# TOF.net
KiCad netlist of a schematic drawn in Altium Designer
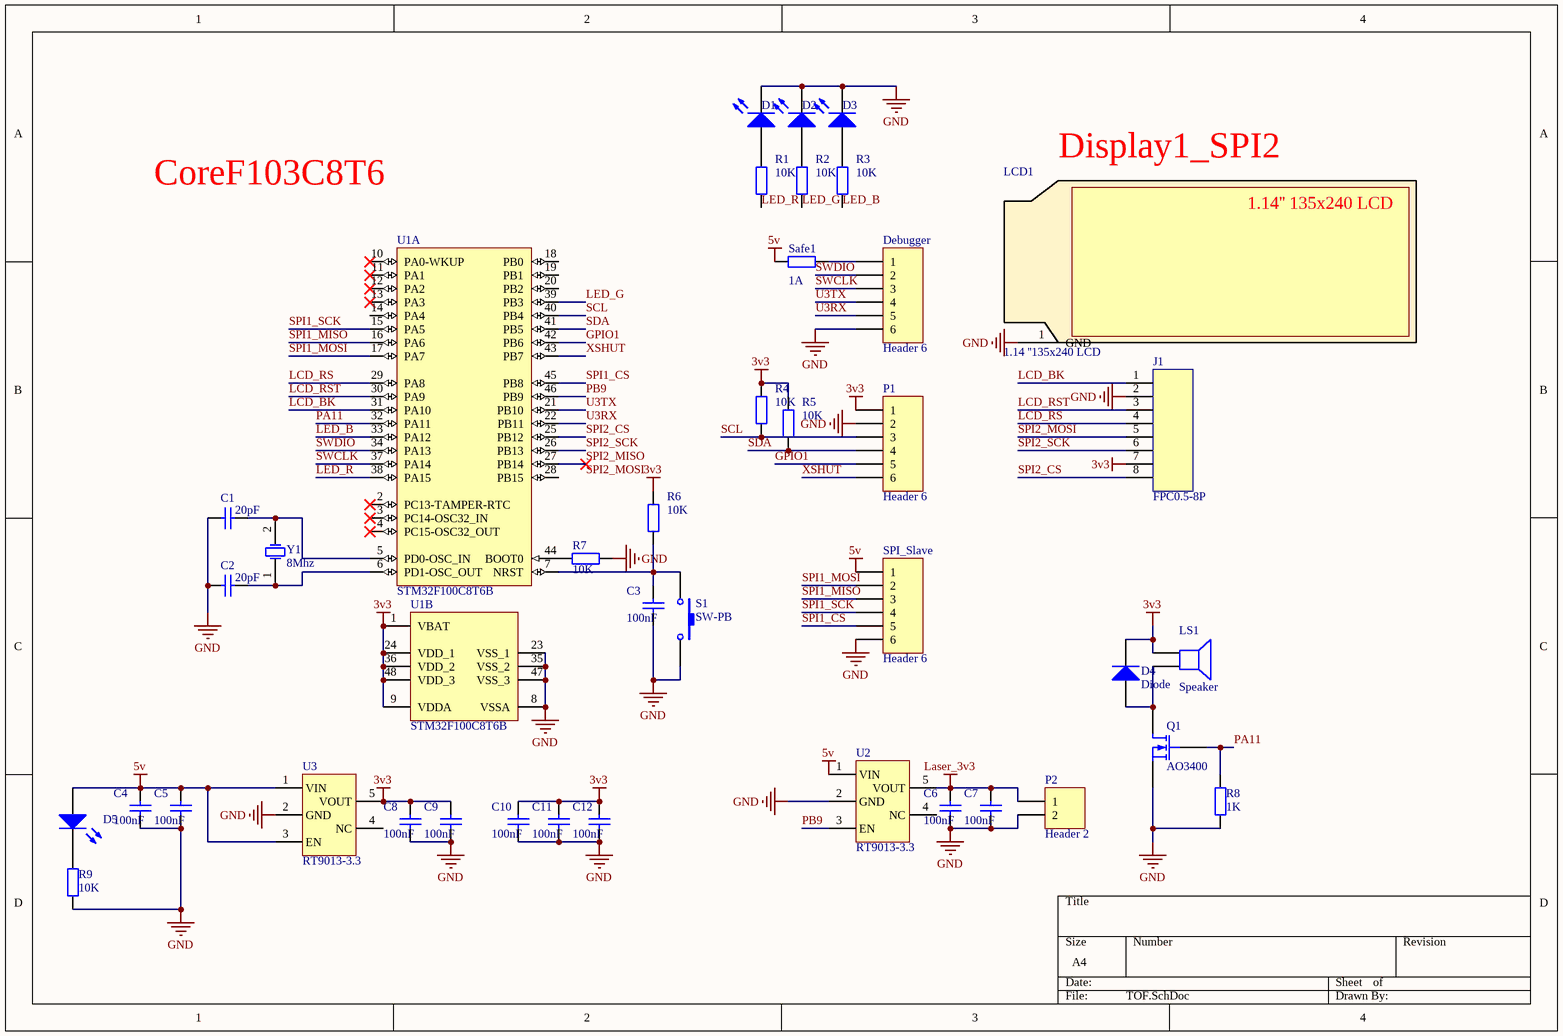
[diagram p0: TOF.SchDoc]

(export (version "E")
  (design (tool "Eeschema 10.0.6"))
  (components
    (comp (ref "C1")
      (value "20pF")
      (footprint "0603C")
      (description "Capacitor")
      (fields (field (name "Comment") "Cap") (field (name "PUBLISHER") "Altium Limited"))
      (libsource (lib "Miscellaneous Devices") (part "Cap"))
    )
    (comp (ref "C2")
      (value "20pF")
      (footprint "0603C")
      (description "Capacitor")
      (fields (field (name "Comment") "Cap") (field (name "PUBLISHER") "Altium Limited"))
      (libsource (lib "Miscellaneous Devices") (part "Cap"))
    )
    (comp (ref "C3")
      (value "100nF")
      (footprint "0603C")
      (description "Capacitor")
      (fields (field (name "Comment") "Cap") (field (name "PUBLISHER") "Altium Limited"))
      (libsource (lib "Miscellaneous Devices") (part "Cap"))
    )
    (comp (ref "C4")
      (value "100nF")
      (footprint "0603C")
      (description "Capacitor")
      (fields (field (name "Comment") "Cap") (field (name "PUBLISHER") "Altium Limited"))
      (libsource (lib "Miscellaneous Devices") (part "Cap"))
    )
    (comp (ref "C5")
      (value "100nF")
      (footprint "0603C")
      (description "Capacitor")
      (fields (field (name "Comment") "Cap") (field (name "PUBLISHER") "Altium Limited"))
      (libsource (lib "Miscellaneous Devices") (part "Cap"))
    )
    (comp (ref "C6")
      (value "100nF")
      (footprint "0603C")
      (description "Capacitor")
      (fields (field (name "Comment") "Cap") (field (name "PUBLISHER") "Altium Limited"))
      (libsource (lib "Miscellaneous Devices") (part "Cap"))
    )
    (comp (ref "C7")
      (value "100nF")
      (footprint "0603C")
      (description "Capacitor")
      (fields (field (name "Comment") "Cap") (field (name "PUBLISHER") "Altium Limited"))
      (libsource (lib "Miscellaneous Devices") (part "Cap"))
    )
    (comp (ref "C8")
      (value "100nF")
      (footprint "0603C")
      (description "Capacitor")
      (fields (field (name "Comment") "Cap") (field (name "PUBLISHER") "Altium Limited"))
      (libsource (lib "Miscellaneous Devices") (part "Cap"))
    )
    (comp (ref "C9")
      (value "100nF")
      (footprint "0603C")
      (description "Capacitor")
      (fields (field (name "Comment") "Cap") (field (name "PUBLISHER") "Altium Limited"))
      (libsource (lib "Miscellaneous Devices") (part "Cap"))
    )
    (comp (ref "C10")
      (value "100nF")
      (footprint "0603C")
      (description "Capacitor")
      (fields (field (name "Comment") "Cap") (field (name "PUBLISHER") "Altium Limited"))
      (libsource (lib "Miscellaneous Devices") (part "Cap"))
    )
    (comp (ref "C11")
      (value "100nF")
      (footprint "0603C")
      (description "Capacitor")
      (fields (field (name "Comment") "Cap") (field (name "PUBLISHER") "Altium Limited"))
      (libsource (lib "Miscellaneous Devices") (part "Cap"))
    )
    (comp (ref "C12")
      (value "100nF")
      (footprint "0603C")
      (description "Capacitor")
      (fields (field (name "Comment") "Cap") (field (name "PUBLISHER") "Altium Limited"))
      (libsource (lib "Miscellaneous Devices") (part "Cap"))
    )
    (comp (ref "D1")
      (value "LED0")
      (footprint "LED-0805-Red")
      (description "Typical INFRARED GaAs LED")
      (fields (field (name "PUBLISHER") "Altium Limited"))
      (libsource (lib "Miscellaneous Devices") (part "LED0"))
    )
    (comp (ref "D2")
      (value "LED0")
      (footprint "0805LED")
      (description "Typical INFRARED GaAs LED")
      (fields (field (name "PUBLISHER") "Altium Limited"))
      (libsource (lib "Miscellaneous Devices") (part "LED0"))
    )
    (comp (ref "D3")
      (value "LED0")
      (footprint "LED-0805-Blue")
      (description "Typical INFRARED GaAs LED")
      (fields (field (name "PUBLISHER") "Altium Limited"))
      (libsource (lib "Miscellaneous Devices") (part "LED0"))
    )
    (comp (ref "D4")
      (value "Diode")
      (footprint "SOD-323-")
      (description "Default Diode")
      (fields (field (name "PUBLISHER") "Altium Limited"))
      (libsource (lib "Miscellaneous Devices") (part "Diode"))
    )
    (comp (ref "D5")
      (value "LED0")
      (footprint "0805LED")
      (description "Typical INFRARED GaAs LED")
      (fields (field (name "PUBLISHER") "Altium Limited"))
      (libsource (lib "Miscellaneous Devices") (part "LED0"))
    )
    (comp (ref "Debugger")
      (value "Header 6")
      (footprint "GX1.25_T_6P")
      (description "Header, 6-Pin")
      (fields (field (name "PUBLISHER") "Altium Limited"))
      (libsource (lib "Miscellaneous Connectors") (part "Header 6"))
    )
    (comp (ref "J1")
      (value "FPC0.5-8P")
      (footprint "FPC0.5-8P")
      (description "贴片")
      (libsource (lib "TOF") (part "FPC0.5-8P"))
    )
    (comp (ref "LCD1")
      (value "1.14 ''135x240 LCD")
      (footprint "1.14'' LCD")
      (libsource (lib "TOF") (part "1.14 ''135x240 LCD"))
    )
    (comp (ref "LS1")
      (value "Speaker")
      (footprint "MLT-8530")
      (description "Loudspeaker")
      (fields (field (name "PUBLISHER") "Altium Limited"))
      (libsource (lib "Miscellaneous Devices") (part "Speaker"))
    )
    (comp (ref "P1")
      (value "Header 6")
      (footprint "HDR1X6")
      (description "Header, 6-Pin")
      (fields (field (name "PUBLISHER") "Altium Limited"))
      (libsource (lib "Miscellaneous Connectors") (part "Header 6"))
    )
    (comp (ref "P2")
      (value "Header 2")
      (footprint "HDR1X2")
      (description "Header, 2-Pin")
      (fields (field (name "PUBLISHER") "Altium Limited"))
      (libsource (lib "Miscellaneous Connectors") (part "Header 2"))
    )
    (comp (ref "Q1")
      (value "AO3400")
      (footprint "SOT-23")
      (description "N-Channel MOSFET")
      (fields (field (name "PUBLISHER") "Altium Limited"))
      (libsource (lib "Miscellaneous Devices") (part "MOSFET-N"))
    )
    (comp (ref "R1")
      (value "10K")
      (footprint "0603R")
      (description "Resistor")
      (fields (field (name "PUBLISHER") "Altium Limited"))
      (libsource (lib "") (part "Res2_1"))
    )
    (comp (ref "R2")
      (value "10K")
      (footprint "0603R")
      (description "Resistor")
      (fields (field (name "PUBLISHER") "Altium Limited"))
      (libsource (lib "") (part "Res2_1"))
    )
    (comp (ref "R3")
      (value "10K")
      (footprint "0603R")
      (description "Resistor")
      (fields (field (name "PUBLISHER") "Altium Limited"))
      (libsource (lib "") (part "Res2_1"))
    )
    (comp (ref "R4")
      (value "10K")
      (footprint "0603R")
      (description "Resistor")
      (fields (field (name "PUBLISHER") "Altium Limited"))
      (libsource (lib "") (part "Res2_1"))
    )
    (comp (ref "R5")
      (value "10K")
      (footprint "0603R")
      (description "Resistor")
      (fields (field (name "PUBLISHER") "Altium Limited"))
      (libsource (lib "") (part "Res2_1"))
    )
    (comp (ref "R6")
      (value "10K")
      (footprint "0603R")
      (description "Resistor")
      (fields (field (name "PUBLISHER") "Altium Limited"))
      (libsource (lib "") (part "Res2_1"))
    )
    (comp (ref "R7")
      (value "10K")
      (footprint "0603R")
      (description "Resistor")
      (fields (field (name "Comment") "Res2") (field (name "PUBLISHER") "Altium Limited"))
      (libsource (lib "") (part "Res2_3"))
    )
    (comp (ref "R8")
      (value "1K")
      (footprint "0603R")
      (description "Resistor")
      (fields (field (name "Comment") "Res2") (field (name "PUBLISHER") "Altium Limited"))
      (libsource (lib "") (part "Res2_1"))
    )
    (comp (ref "R9")
      (value "10K")
      (footprint "0603R")
      (description "Resistor")
      (fields (field (name "PUBLISHER") "Altium Limited"))
      (libsource (lib "") (part "Res2_2"))
    )
    (comp (ref "S1")
      (value "SW-PB")
      (footprint "Key-2*4*3.5-S")
      (description "Switch")
      (fields (field (name "PUBLISHER") "Altium Limited"))
      (libsource (lib "Miscellaneous Devices") (part "SW-PB"))
    )
    (comp (ref "Safe1")
      (value "1A")
      (footprint "Maxwell_LIB:0805R")
      (description "Resistor")
      (fields (field (name "Comment") "Res2") (field (name "PUBLISHER") "Altium Limited"))
      (libsource (lib "Miscellaneous Devices") (part "Res2"))
    )
    (comp (ref "SPI_Slave")
      (value "Header 6")
      (footprint "GX1.25_T_6P")
      (description "Header, 6-Pin")
      (fields (field (name "PUBLISHER") "Altium Limited"))
      (libsource (lib "Miscellaneous Connectors") (part "Header 6"))
    )
    (comp (ref "U1")
      (value "STM32F100C8T6B")
      (footprint "STM-LQFP48_N")
      (libsource (lib "STM32F1") (part "STM32F100C8T6B"))
    )
    (comp (ref "U2")
      (value "RT9013-3.3")
      (footprint "SOT-23-5")
      (description "3.3V 500mA")
      (libsource (lib "My_Library") (part "RT9013"))
    )
    (comp (ref "U3")
      (value "RT9013-3.3")
      (footprint "SOT-23-5")
      (description "3.3V 500mA")
      (libsource (lib "My_Library") (part "RT9013"))
    )
    (comp (ref "Y1")
      (value "8Mhz")
      (footprint "Cry-3215")
      (fields (field (name "PUBLISHER") "Altium Limited"))
      (libsource (lib "Miscellaneous Devices") (part "XTAL"))
    )
  )
  (nets
    (net (code "1") (name "/GPIO1") (class "Default")
      (node (ref "P1") (pin "5") (pinfunction "5_5") (pintype "passive"))
      (node (ref "U1") (pin "42") (pinfunction "PB6_42") (pintype "bidirectional"))
    )
    (net (code "2") (name "/LCD_BK") (class "Default")
      (node (ref "J1") (pin "1") (pinfunction "1_1") (pintype "passive"))
      (node (ref "U1") (pin "31") (pinfunction "PA10_31") (pintype "bidirectional"))
    )
    (net (code "3") (name "/LCD_RS") (class "Default")
      (node (ref "J1") (pin "4") (pinfunction "4_4") (pintype "passive"))
      (node (ref "U1") (pin "29") (pinfunction "PA8_29") (pintype "bidirectional"))
    )
    (net (code "4") (name "/LCD_RST") (class "Default")
      (node (ref "J1") (pin "3") (pinfunction "3_3") (pintype "passive"))
      (node (ref "U1") (pin "30") (pinfunction "PA9_30") (pintype "bidirectional"))
    )
    (net (code "5") (name "/LED_B") (class "Default")
      (node (ref "R3") (pin "1") (pinfunction "1_1") (pintype "passive"))
      (node (ref "U1") (pin "33") (pinfunction "PA12_33") (pintype "bidirectional"))
    )
    (net (code "6") (name "/LED_G") (class "Default")
      (node (ref "R2") (pin "1") (pinfunction "1_1") (pintype "passive"))
      (node (ref "U1") (pin "39") (pinfunction "PB3_39") (pintype "bidirectional"))
    )
    (net (code "7") (name "/LED_R") (class "Default")
      (node (ref "R1") (pin "1") (pinfunction "1_1") (pintype "passive"))
      (node (ref "U1") (pin "38") (pinfunction "PA15_38") (pintype "bidirectional"))
    )
    (net (code "8") (name "/PA11") (class "Default")
      (node (ref "Q1") (pin "2") (pinfunction "G_2") (pintype "passive"))
      (node (ref "R8") (pin "2") (pinfunction "2_2") (pintype "passive"))
      (node (ref "U1") (pin "32") (pinfunction "PA11_32") (pintype "bidirectional"))
    )
    (net (code "9") (name "/PB9") (class "Default")
      (node (ref "U1") (pin "46") (pinfunction "PB9_46") (pintype "bidirectional"))
      (node (ref "U2") (pin "3") (pinfunction "EN_3") (pintype "passive"))
    )
    (net (code "10") (name "/SCL") (class "Default")
      (node (ref "P1") (pin "3") (pinfunction "3_3") (pintype "passive"))
      (node (ref "R4") (pin "1") (pinfunction "1_1") (pintype "passive"))
      (node (ref "U1") (pin "40") (pinfunction "PB4_40") (pintype "bidirectional"))
    )
    (net (code "11") (name "/SDA") (class "Default")
      (node (ref "P1") (pin "4") (pinfunction "4_4") (pintype "passive"))
      (node (ref "R5") (pin "1") (pinfunction "1_1") (pintype "passive"))
      (node (ref "U1") (pin "41") (pinfunction "PB5_41") (pintype "bidirectional"))
    )
    (net (code "12") (name "/SPI1_CS") (class "Default")
      (node (ref "SPI_Slave") (pin "5") (pinfunction "5_5") (pintype "passive"))
      (node (ref "U1") (pin "45") (pinfunction "PB8_45") (pintype "bidirectional"))
    )
    (net (code "13") (name "/SPI1_MISO") (class "Default")
      (node (ref "SPI_Slave") (pin "3") (pinfunction "3_3") (pintype "passive"))
      (node (ref "U1") (pin "16") (pinfunction "PA6_16") (pintype "bidirectional"))
    )
    (net (code "14") (name "/SPI1_MOSI") (class "Default")
      (node (ref "SPI_Slave") (pin "2") (pinfunction "2_2") (pintype "passive"))
      (node (ref "U1") (pin "17") (pinfunction "PA7_17") (pintype "bidirectional"))
    )
    (net (code "15") (name "/SPI1_SCK") (class "Default")
      (node (ref "SPI_Slave") (pin "4") (pinfunction "4_4") (pintype "passive"))
      (node (ref "U1") (pin "15") (pinfunction "PA5_15") (pintype "bidirectional"))
    )
    (net (code "16") (name "/SPI2_CS") (class "Default")
      (node (ref "J1") (pin "8") (pinfunction "8_8") (pintype "passive"))
      (node (ref "U1") (pin "25") (pinfunction "PB12_25") (pintype "bidirectional"))
    )
    (net (code "17") (name "/SPI2_MISO") (class "Default")
      (node (ref "U1") (pin "27") (pinfunction "PB14_27") (pintype "bidirectional+no_connect"))
    )
    (net (code "18") (name "/SPI2_MOSI") (class "Default")
      (node (ref "J1") (pin "5") (pinfunction "5_5") (pintype "passive"))
    )
    (net (code "19") (name "/SPI2_SCK") (class "Default")
      (node (ref "J1") (pin "6") (pinfunction "6_6") (pintype "passive"))
      (node (ref "U1") (pin "26") (pinfunction "PB13_26") (pintype "bidirectional"))
    )
    (net (code "20") (name "/SWCLK") (class "Default")
      (node (ref "Debugger") (pin "3") (pinfunction "3_3") (pintype "passive"))
      (node (ref "U1") (pin "37") (pinfunction "PA14_37") (pintype "bidirectional"))
    )
    (net (code "21") (name "/SWDIO") (class "Default")
      (node (ref "Debugger") (pin "2") (pinfunction "2_2") (pintype "passive"))
      (node (ref "U1") (pin "34") (pinfunction "PA13_34") (pintype "bidirectional"))
    )
    (net (code "22") (name "/U3RX") (class "Default")
      (node (ref "Debugger") (pin "5") (pinfunction "5_5") (pintype "passive"))
      (node (ref "U1") (pin "22") (pinfunction "PB11_22") (pintype "bidirectional"))
    )
    (net (code "23") (name "/U3TX") (class "Default")
      (node (ref "Debugger") (pin "4") (pinfunction "4_4") (pintype "passive"))
      (node (ref "U1") (pin "21") (pinfunction "PB10_21") (pintype "bidirectional"))
    )
    (net (code "24") (name "/XSHUT") (class "Default")
      (node (ref "P1") (pin "6") (pinfunction "6_6") (pintype "passive"))
      (node (ref "U1") (pin "43") (pinfunction "PB7_43") (pintype "bidirectional"))
    )
    (net (code "25") (name "3v3") (class "Default")
      (node (ref "C10") (pin "2") (pinfunction "2_2") (pintype "passive"))
      (node (ref "C11") (pin "2") (pinfunction "2_2") (pintype "passive"))
      (node (ref "C12") (pin "2") (pinfunction "2_2") (pintype "passive"))
      (node (ref "C8") (pin "2") (pinfunction "2_2") (pintype "passive"))
      (node (ref "C9") (pin "2") (pinfunction "2_2") (pintype "passive"))
      (node (ref "D4") (pin "2") (pinfunction "K_2") (pintype "passive"))
      (node (ref "J1") (pin "7") (pinfunction "7_7") (pintype "passive"))
      (node (ref "LS1") (pin "1") (pinfunction "1_1") (pintype "passive"))
      (node (ref "P1") (pin "1") (pinfunction "1_1") (pintype "passive"))
      (node (ref "R4") (pin "2") (pinfunction "2_2") (pintype "passive"))
      (node (ref "R5") (pin "2") (pinfunction "2_2") (pintype "passive"))
      (node (ref "R6") (pin "2") (pinfunction "2_2") (pintype "passive"))
      (node (ref "U1") (pin "1") (pinfunction "VBAT_1") (pintype "power_in"))
      (node (ref "U1") (pin "24") (pinfunction "VDD_1_24") (pintype "power_in"))
      (node (ref "U1") (pin "36") (pinfunction "VDD_2_36") (pintype "power_in"))
      (node (ref "U1") (pin "48") (pinfunction "VDD_3_48") (pintype "power_in"))
      (node (ref "U1") (pin "9") (pinfunction "VDDA_9") (pintype "power_in"))
      (node (ref "U3") (pin "5") (pinfunction "VOUT_5") (pintype "passive"))
    )
    (net (code "26") (name "5v") (class "Default")
      (node (ref "C4") (pin "2") (pinfunction "2_2") (pintype "passive"))
      (node (ref "C5") (pin "2") (pinfunction "2_2") (pintype "passive"))
      (node (ref "D5") (pin "1") (pinfunction "A_1") (pintype "passive"))
      (node (ref "SPI_Slave") (pin "1") (pinfunction "1_1") (pintype "passive"))
      (node (ref "Safe1") (pin "1") (pinfunction "1_1") (pintype "passive"))
      (node (ref "U2") (pin "1") (pinfunction "VIN_1") (pintype "passive"))
      (node (ref "U3") (pin "1") (pinfunction "VIN_1") (pintype "passive"))
      (node (ref "U3") (pin "3") (pinfunction "EN_3") (pintype "passive"))
    )
    (net (code "27") (name "GND") (class "Default")
      (node (ref "C1") (pin "1") (pinfunction "1_1") (pintype "passive"))
      (node (ref "C10") (pin "1") (pinfunction "1_1") (pintype "passive"))
      (node (ref "C11") (pin "1") (pinfunction "1_1") (pintype "passive"))
      (node (ref "C12") (pin "1") (pinfunction "1_1") (pintype "passive"))
      (node (ref "C2") (pin "1") (pinfunction "1_1") (pintype "passive"))
      (node (ref "C3") (pin "1") (pinfunction "1_1") (pintype "passive"))
      (node (ref "C4") (pin "1") (pinfunction "1_1") (pintype "passive"))
      (node (ref "C5") (pin "1") (pinfunction "1_1") (pintype "passive"))
      (node (ref "C6") (pin "1") (pinfunction "1_1") (pintype "passive"))
      (node (ref "C7") (pin "1") (pinfunction "1_1") (pintype "passive"))
      (node (ref "C8") (pin "1") (pinfunction "1_1") (pintype "passive"))
      (node (ref "C9") (pin "1") (pinfunction "1_1") (pintype "passive"))
      (node (ref "D1") (pin "2") (pinfunction "K_2") (pintype "passive"))
      (node (ref "D2") (pin "2") (pinfunction "K_2") (pintype "passive"))
      (node (ref "D3") (pin "2") (pinfunction "K_2") (pintype "passive"))
      (node (ref "Debugger") (pin "6") (pinfunction "6_6") (pintype "passive"))
      (node (ref "J1") (pin "2") (pinfunction "2_2") (pintype "passive"))
      (node (ref "LCD1") (pin "1") (pinfunction "GND_1") (pintype "passive"))
      (node (ref "P1") (pin "2") (pinfunction "2_2") (pintype "passive"))
      (node (ref "P2") (pin "2") (pinfunction "2_2") (pintype "passive"))
      (node (ref "Q1") (pin "3") (pinfunction "S_3") (pintype "passive"))
      (node (ref "R7") (pin "1") (pinfunction "1_1") (pintype "passive"))
      (node (ref "R8") (pin "1") (pinfunction "1_1") (pintype "passive"))
      (node (ref "R9") (pin "2") (pinfunction "2_2") (pintype "passive"))
      (node (ref "S1") (pin "2") (pinfunction "2_2") (pintype "passive"))
      (node (ref "SPI_Slave") (pin "6") (pinfunction "6_6") (pintype "passive"))
      (node (ref "U1") (pin "23") (pinfunction "VSS_1_23") (pintype "power_in"))
      (node (ref "U1") (pin "35") (pinfunction "VSS_2_35") (pintype "power_in"))
      (node (ref "U1") (pin "47") (pinfunction "VSS_3_47") (pintype "power_in"))
      (node (ref "U1") (pin "8") (pinfunction "VSSA_8") (pintype "power_in"))
      (node (ref "U2") (pin "2") (pinfunction "GND_2") (pintype "passive"))
      (node (ref "U3") (pin "2") (pinfunction "GND_2") (pintype "passive"))
    )
    (net (code "28") (name "Laser_3v3") (class "Default")
      (node (ref "C6") (pin "2") (pinfunction "2_2") (pintype "passive"))
      (node (ref "C7") (pin "2") (pinfunction "2_2") (pintype "passive"))
      (node (ref "P2") (pin "1") (pinfunction "1_1") (pintype "passive"))
      (node (ref "U2") (pin "5") (pinfunction "VOUT_5") (pintype "passive"))
    )
    (net (code "29") (name "Net-(D1-A)") (class "Default")
      (node (ref "D1") (pin "1") (pinfunction "A_1") (pintype "passive"))
      (node (ref "R1") (pin "2") (pinfunction "2_2") (pintype "passive"))
    )
    (net (code "30") (name "Net-(D2-A)") (class "Default")
      (node (ref "D2") (pin "1") (pinfunction "A_1") (pintype "passive"))
      (node (ref "R2") (pin "2") (pinfunction "2_2") (pintype "passive"))
    )
    (net (code "31") (name "Net-(D3-A)") (class "Default")
      (node (ref "D3") (pin "1") (pinfunction "A_1") (pintype "passive"))
      (node (ref "R3") (pin "2") (pinfunction "2_2") (pintype "passive"))
    )
    (net (code "32") (name "Net-(D4-A)") (class "Default")
      (node (ref "D4") (pin "1") (pinfunction "A_1") (pintype "passive"))
      (node (ref "LS1") (pin "2") (pinfunction "2_2") (pintype "passive"))
      (node (ref "Q1") (pin "1") (pinfunction "D_1") (pintype "passive"))
    )
    (net (code "33") (name "Net-(D5-K)") (class "Default")
      (node (ref "D5") (pin "2") (pinfunction "K_2") (pintype "passive"))
      (node (ref "R9") (pin "1") (pinfunction "1_1") (pintype "passive"))
    )
    (net (code "34") (name "Net-(Debugger-Pad1)") (class "Default")
      (node (ref "Debugger") (pin "1") (pinfunction "1_1") (pintype "passive"))
      (node (ref "Safe1") (pin "2") (pinfunction "2_2") (pintype "passive"))
    )
    (net (code "35") (name "Net-(U1A-BOOT0)") (class "Default")
      (node (ref "R7") (pin "2") (pinfunction "2_2") (pintype "passive"))
      (node (ref "U1") (pin "44") (pinfunction "BOOT0_44") (pintype "input"))
    )
    (net (code "36") (name "Net-(U1A-NRST)") (class "Default")
      (node (ref "C3") (pin "2") (pinfunction "2_2") (pintype "passive"))
      (node (ref "R6") (pin "1") (pinfunction "1_1") (pintype "passive"))
      (node (ref "S1") (pin "1") (pinfunction "1_1") (pintype "passive"))
      (node (ref "U1") (pin "7") (pinfunction "NRST_7") (pintype "bidirectional"))
    )
    (net (code "37") (name "Net-(U1A-PD0-OSC_IN)") (class "Default")
      (node (ref "C1") (pin "2") (pinfunction "2_2") (pintype "passive"))
      (node (ref "U1") (pin "5") (pinfunction "PD0-OSC_IN_5") (pintype "bidirectional"))
      (node (ref "Y1") (pin "2") (pinfunction "OSC2_2") (pintype "passive"))
    )
    (net (code "38") (name "Net-(U1A-PD1-OSC_OUT)") (class "Default")
      (node (ref "C2") (pin "2") (pinfunction "2_2") (pintype "passive"))
      (node (ref "U1") (pin "6") (pinfunction "PD1-OSC_OUT_6") (pintype "bidirectional"))
      (node (ref "Y1") (pin "1") (pinfunction "OSC1_1") (pintype "passive"))
    )
    (net (code "39") (name "unconnected-(U1A-PA0-WKUP-Pad10)") (class "Default")
      (node (ref "U1") (pin "10") (pinfunction "PA0-WKUP_10") (pintype "bidirectional+no_connect"))
    )
    (net (code "40") (name "unconnected-(U1A-PA1-Pad11)") (class "Default")
      (node (ref "U1") (pin "11") (pinfunction "PA1_11") (pintype "bidirectional+no_connect"))
    )
    (net (code "41") (name "unconnected-(U1A-PA2-Pad12)") (class "Default")
      (node (ref "U1") (pin "12") (pinfunction "PA2_12") (pintype "bidirectional+no_connect"))
    )
    (net (code "42") (name "unconnected-(U1A-PA3-Pad13)") (class "Default")
      (node (ref "U1") (pin "13") (pinfunction "PA3_13") (pintype "bidirectional+no_connect"))
    )
    (net (code "43") (name "unconnected-(U1A-PA4-Pad14)") (class "Default")
      (node (ref "U1") (pin "14") (pinfunction "PA4_14") (pintype "bidirectional"))
    )
    (net (code "44") (name "unconnected-(U1A-PB0-Pad18)") (class "Default")
      (node (ref "U1") (pin "18") (pinfunction "PB0_18") (pintype "bidirectional"))
    )
    (net (code "45") (name "unconnected-(U1A-PB1-Pad19)") (class "Default")
      (node (ref "U1") (pin "19") (pinfunction "PB1_19") (pintype "bidirectional"))
    )
    (net (code "46") (name "unconnected-(U1A-PB2-Pad20)") (class "Default")
      (node (ref "U1") (pin "20") (pinfunction "PB2_20") (pintype "bidirectional"))
    )
    (net (code "47") (name "unconnected-(U1A-PB15-Pad28)") (class "Default")
      (node (ref "U1") (pin "28") (pinfunction "PB15_28") (pintype "bidirectional"))
    )
    (net (code "48") (name "unconnected-(U1A-PC13-TAMPER-RTC-Pad2)") (class "Default")
      (node (ref "U1") (pin "2") (pinfunction "PC13-TAMPER-RTC_2") (pintype "bidirectional+no_connect"))
    )
    (net (code "49") (name "unconnected-(U1A-PC14-OSC32_IN-Pad3)") (class "Default")
      (node (ref "U1") (pin "3") (pinfunction "PC14-OSC32_IN_3") (pintype "bidirectional+no_connect"))
    )
    (net (code "50") (name "unconnected-(U1A-PC15-OSC32_OUT-Pad4)") (class "Default")
      (node (ref "U1") (pin "4") (pinfunction "PC15-OSC32_OUT_4") (pintype "bidirectional+no_connect"))
    )
    (net (code "51") (name "unconnected-(U2-NC-Pad4)") (class "Default")
      (node (ref "U2") (pin "4") (pinfunction "NC_4") (pintype "passive"))
    )
    (net (code "52") (name "unconnected-(U3-NC-Pad4)") (class "Default")
      (node (ref "U3") (pin "4") (pinfunction "NC_4") (pintype "passive"))
    )
  )
)
